# Ideal_Diode.net
KiCad netlist of a schematic drawn in Altium Designer
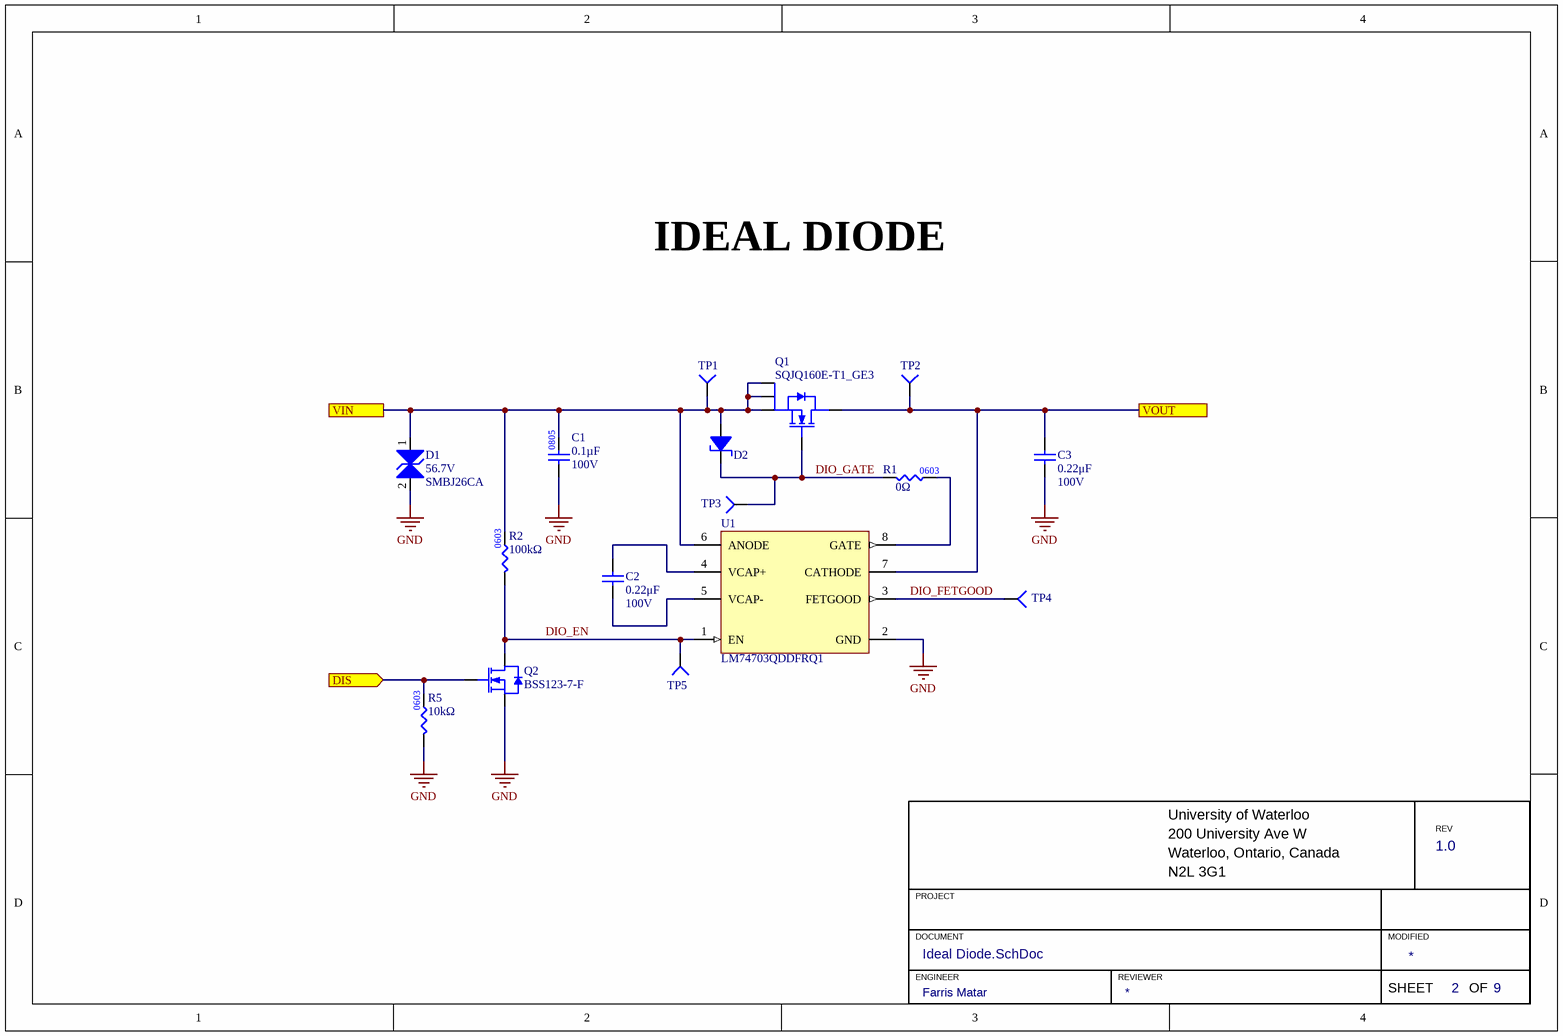
[diagram p0: Ideal Diode.SchDoc]

(export (version "E")
  (design (tool "Eeschema 10.0.6"))
  (components
    (comp (ref "C1")
      (value "0.1µF")
      (footprint "CAP0805")
      (description "CAP CER 0.1UF 100V X7R 0805")
      (fields (field (name "VOLTAGE RATING") "100V") (field (name "Comment") "CAP_0.1uF_100V_0805"))
      (libsource (lib "Personal_Schematic_Library_2022") (part "CAP_0.1uF_100V_0805"))
    )
    (comp (ref "C2")
      (value "0.22μF")
      (footprint "CAP0805")
      (description "CAP CER 0.22UF 100V X7R 0805")
      (fields (field (name "VOLTAGE RATING") "100V") (field (name "Comment") "CAP_0.22uF_100V_0805"))
      (libsource (lib "Personal_Schematic_Library_2022") (part "CAP_0.22uF_100V_0805"))
    )
    (comp (ref "C3")
      (value "0.22μF")
      (footprint "CAP0805")
      (description "CAP CER 0.22UF 100V X7R 0805")
      (fields (field (name "VOLTAGE RATING") "100V") (field (name "Comment") "CAP_0.22uF_100V_0805"))
      (libsource (lib "Personal_Schematic_Library_2022") (part "CAP_0.22uF_100V_0805"))
    )
    (comp (ref "D1")
      (value "TVS_DIODE_BIDIR_51V")
      (footprint "TVS_DIODE_BIDIR_SMB")
      (description "TVS DIODE 51VWM 82.4VC DO214AA")
      (fields
        (field (name "VOLTAGE - BREAKDOWN (MIN)") "56.7V")
        (field (name "MANUFACTURER PART NUMBER 1") "SMBJ26CA")
      )
      (libsource (lib "Personal_Schematic_Library_2022") (part "TVS_DIODE_BIDIR_51V"))
    )
    (comp (ref "D2")
      (value "DIO_ZENER_16V")
      (footprint "SOD-123_FLAT")
      (description "DIODE ZENER 16V 500MW SOD123")
      (libsource (lib "Personal_Schematic_Library_2022") (part "DIO_ZENER_16V"))
    )
    (comp (ref "Q1")
      (value "NMOS_60V_603A")
      (footprint "VISHAY_PowerPAK-8x8")
      (description "AUTOMOTIVE N-CHANNEL 60 V (D-S)")
      (fields (field (name "MANUFACTURER PART NUMBER 1") "SQJQ160E-T1_GE3"))
      (libsource (lib "Personal_Schematic_Library_2022") (part "NMOS_60V_603A"))
    )
    (comp (ref "Q2")
      (value "NMOS_100V_170mA")
      (footprint "SOT23-3")
      (description "MOSFET N-CH 100V 170MA SOT23-3")
      (fields (field (name "MANUFACTURER PART NUMBER 1") "BSS123-7-F"))
      (libsource (lib "Personal_Schematic_Library_2022") (part "NMOS_100V_170mA"))
    )
    (comp (ref "R1")
      (value "0Ω")
      (footprint "RES0603")
      (description "RES 0 OHM JUMPER 1/10W 0603")
      (fields (field (name "Comment") "RES_0Ω_0603"))
      (libsource (lib "Personal_Schematic_Library_2022") (part "RES_0Ω_0603"))
    )
    (comp (ref "R2")
      (value "100kΩ")
      (footprint "RES0603")
      (description "RES 100K OHM 1% 1/10W 0603")
      (fields (field (name "Comment") "RES_100kΩ_0603_1%"))
      (libsource (lib "Personal_Schematic_Library_2022") (part "RES_100kΩ_0603_1%"))
    )
    (comp (ref "R5")
      (value "10kΩ")
      (footprint "RES0603")
      (description "RES 10K OHM 1% 1/8W 0603")
      (fields (field (name "Comment") "RES_10kΩ_0603_1%"))
      (libsource (lib "Personal_Schematic_Library_2022") (part "RES_10kΩ_0603_1%"))
    )
    (comp (ref "TP1")
      (value "TESTPOINT_1MM_SQUARE")
      (footprint "TESTPOINT_SQUARE_1MM")
      (description "TESTPOINT 1MM SQUARE")
      (libsource (lib "Personal_Schematic_Library_2022") (part "TESTPOINT_1MM_SQUARE"))
    )
    (comp (ref "TP2")
      (value "TESTPOINT_1MM_SQUARE")
      (footprint "TESTPOINT_SQUARE_1MM")
      (description "TESTPOINT 1MM SQUARE")
      (libsource (lib "Personal_Schematic_Library_2022") (part "TESTPOINT_1MM_SQUARE"))
    )
    (comp (ref "TP3")
      (value "TESTPOINT_1MM_CIRCLE")
      (footprint "TESTPOINT_CIRCLE_1MM")
      (description "TESTPOINT 1MM CIRCLE")
      (libsource (lib "Personal_Schematic_Library_2022") (part "TESTPOINT_1MM_CIRCLE"))
    )
    (comp (ref "TP4")
      (value "TESTPOINT_1MM_CIRCLE")
      (footprint "TESTPOINT_CIRCLE_1MM")
      (description "TESTPOINT 1MM CIRCLE")
      (libsource (lib "Personal_Schematic_Library_2022") (part "TESTPOINT_1MM_CIRCLE"))
    )
    (comp (ref "TP5")
      (value "TESTPOINT_1MM_CIRCLE")
      (footprint "TESTPOINT_CIRCLE_1MM")
      (description "TESTPOINT 1MM CIRCLE")
      (libsource (lib "Personal_Schematic_Library_2022") (part "TESTPOINT_1MM_CIRCLE"))
    )
    (comp (ref "U1")
      (value "LM74703QDDFRQ1")
      (footprint "TI_SOT23-8")
      (description "AUTOMOTIVE IDEAL DIODE CONTROLLE")
      (libsource (lib "Personal_Schematic_Library_2022") (part "LM74703QDDFRQ1"))
    )
  )
  (nets
    (net (code "1") (name "/DIO_EN") (class "Default")
      (node (ref "Q2") (pin "3") (pinfunction "DRAIN_3") (pintype "passive"))
      (node (ref "R2") (pin "1") (pinfunction "1_1") (pintype "passive"))
      (node (ref "TP5") (pin "1") (pinfunction "=value_1") (pintype "passive"))
      (node (ref "U1") (pin "1") (pinfunction "EN_1") (pintype "input"))
    )
    (net (code "2") (name "/DIO_FETGOOD") (class "Default")
      (node (ref "TP4") (pin "1") (pinfunction "=value_1") (pintype "passive"))
      (node (ref "U1") (pin "3") (pinfunction "FETGOOD_3") (pintype "output"))
    )
    (net (code "3") (name "/DIO_GATE") (class "Default")
      (node (ref "D2") (pin "2") (pinfunction "Cathode_2") (pintype "passive"))
      (node (ref "Q1") (pin "1") (pinfunction "Gate_1") (pintype "passive"))
      (node (ref "R1") (pin "1") (pinfunction "1_1") (pintype "passive"))
      (node (ref "TP3") (pin "1") (pinfunction "=value_1") (pintype "passive"))
    )
    (net (code "4") (name "/DIS") (class "Default")
      (node (ref "Q2") (pin "1") (pinfunction "GATE_1") (pintype "passive"))
      (node (ref "R5") (pin "2") (pinfunction "2_2") (pintype "passive"))
    )
    (net (code "5") (name "/VIN") (class "Default")
      (node (ref "C1") (pin "2") (pinfunction "2_2") (pintype "passive"))
      (node (ref "D1") (pin "1") (pinfunction "1_1") (pintype "passive"))
      (node (ref "D2") (pin "1") (pinfunction "Anode_1") (pintype "passive"))
      (node (ref "Q1") (pin "2") (pinfunction "Source_2") (pintype "passive"))
      (node (ref "Q1") (pin "3") (pinfunction "Source_3") (pintype "passive"))
      (node (ref "Q1") (pin "4") (pinfunction "Source_4") (pintype "passive"))
      (node (ref "R2") (pin "2") (pinfunction "2_2") (pintype "passive"))
      (node (ref "TP1") (pin "1") (pinfunction "=value_1") (pintype "passive"))
      (node (ref "U1") (pin "6") (pinfunction "ANODE_6") (pintype "power_in"))
    )
    (net (code "6") (name "/VOUT") (class "Default")
      (node (ref "C3") (pin "2") (pinfunction "2_2") (pintype "passive"))
      (node (ref "Q1") (pin "5") (pinfunction "Drain_5") (pintype "passive"))
      (node (ref "TP2") (pin "1") (pinfunction "=value_1") (pintype "passive"))
      (node (ref "U1") (pin "7") (pinfunction "CATHODE_7") (pintype "power_in"))
    )
    (net (code "7") (name "GND") (class "Default")
      (node (ref "C1") (pin "1") (pinfunction "1_1") (pintype "passive"))
      (node (ref "C3") (pin "1") (pinfunction "1_1") (pintype "passive"))
      (node (ref "D1") (pin "2") (pinfunction "2_2") (pintype "passive"))
      (node (ref "Q2") (pin "2") (pinfunction "SOURCE_2") (pintype "passive"))
      (node (ref "R5") (pin "1") (pinfunction "1_1") (pintype "passive"))
      (node (ref "U1") (pin "2") (pinfunction "GND_2") (pintype "power_in"))
    )
    (net (code "8") (name "Net-(U1-GATE)") (class "Default")
      (node (ref "R1") (pin "2") (pinfunction "2_2") (pintype "passive"))
      (node (ref "U1") (pin "8") (pinfunction "GATE_8") (pintype "output"))
    )
    (net (code "9") (name "Net-(U1-VCAP+)") (class "Default")
      (node (ref "C2") (pin "2") (pinfunction "2_2") (pintype "passive"))
      (node (ref "U1") (pin "4") (pinfunction "VCAP+_4") (pintype "power_in"))
    )
    (net (code "10") (name "Net-(U1-VCAP-)") (class "Default")
      (node (ref "C2") (pin "1") (pinfunction "1_1") (pintype "passive"))
      (node (ref "U1") (pin "5") (pinfunction "VCAP-_5") (pintype "power_in"))
    )
  )
)
